# VGA.net
KiCad netlist of a schematic drawn in Altium Designer
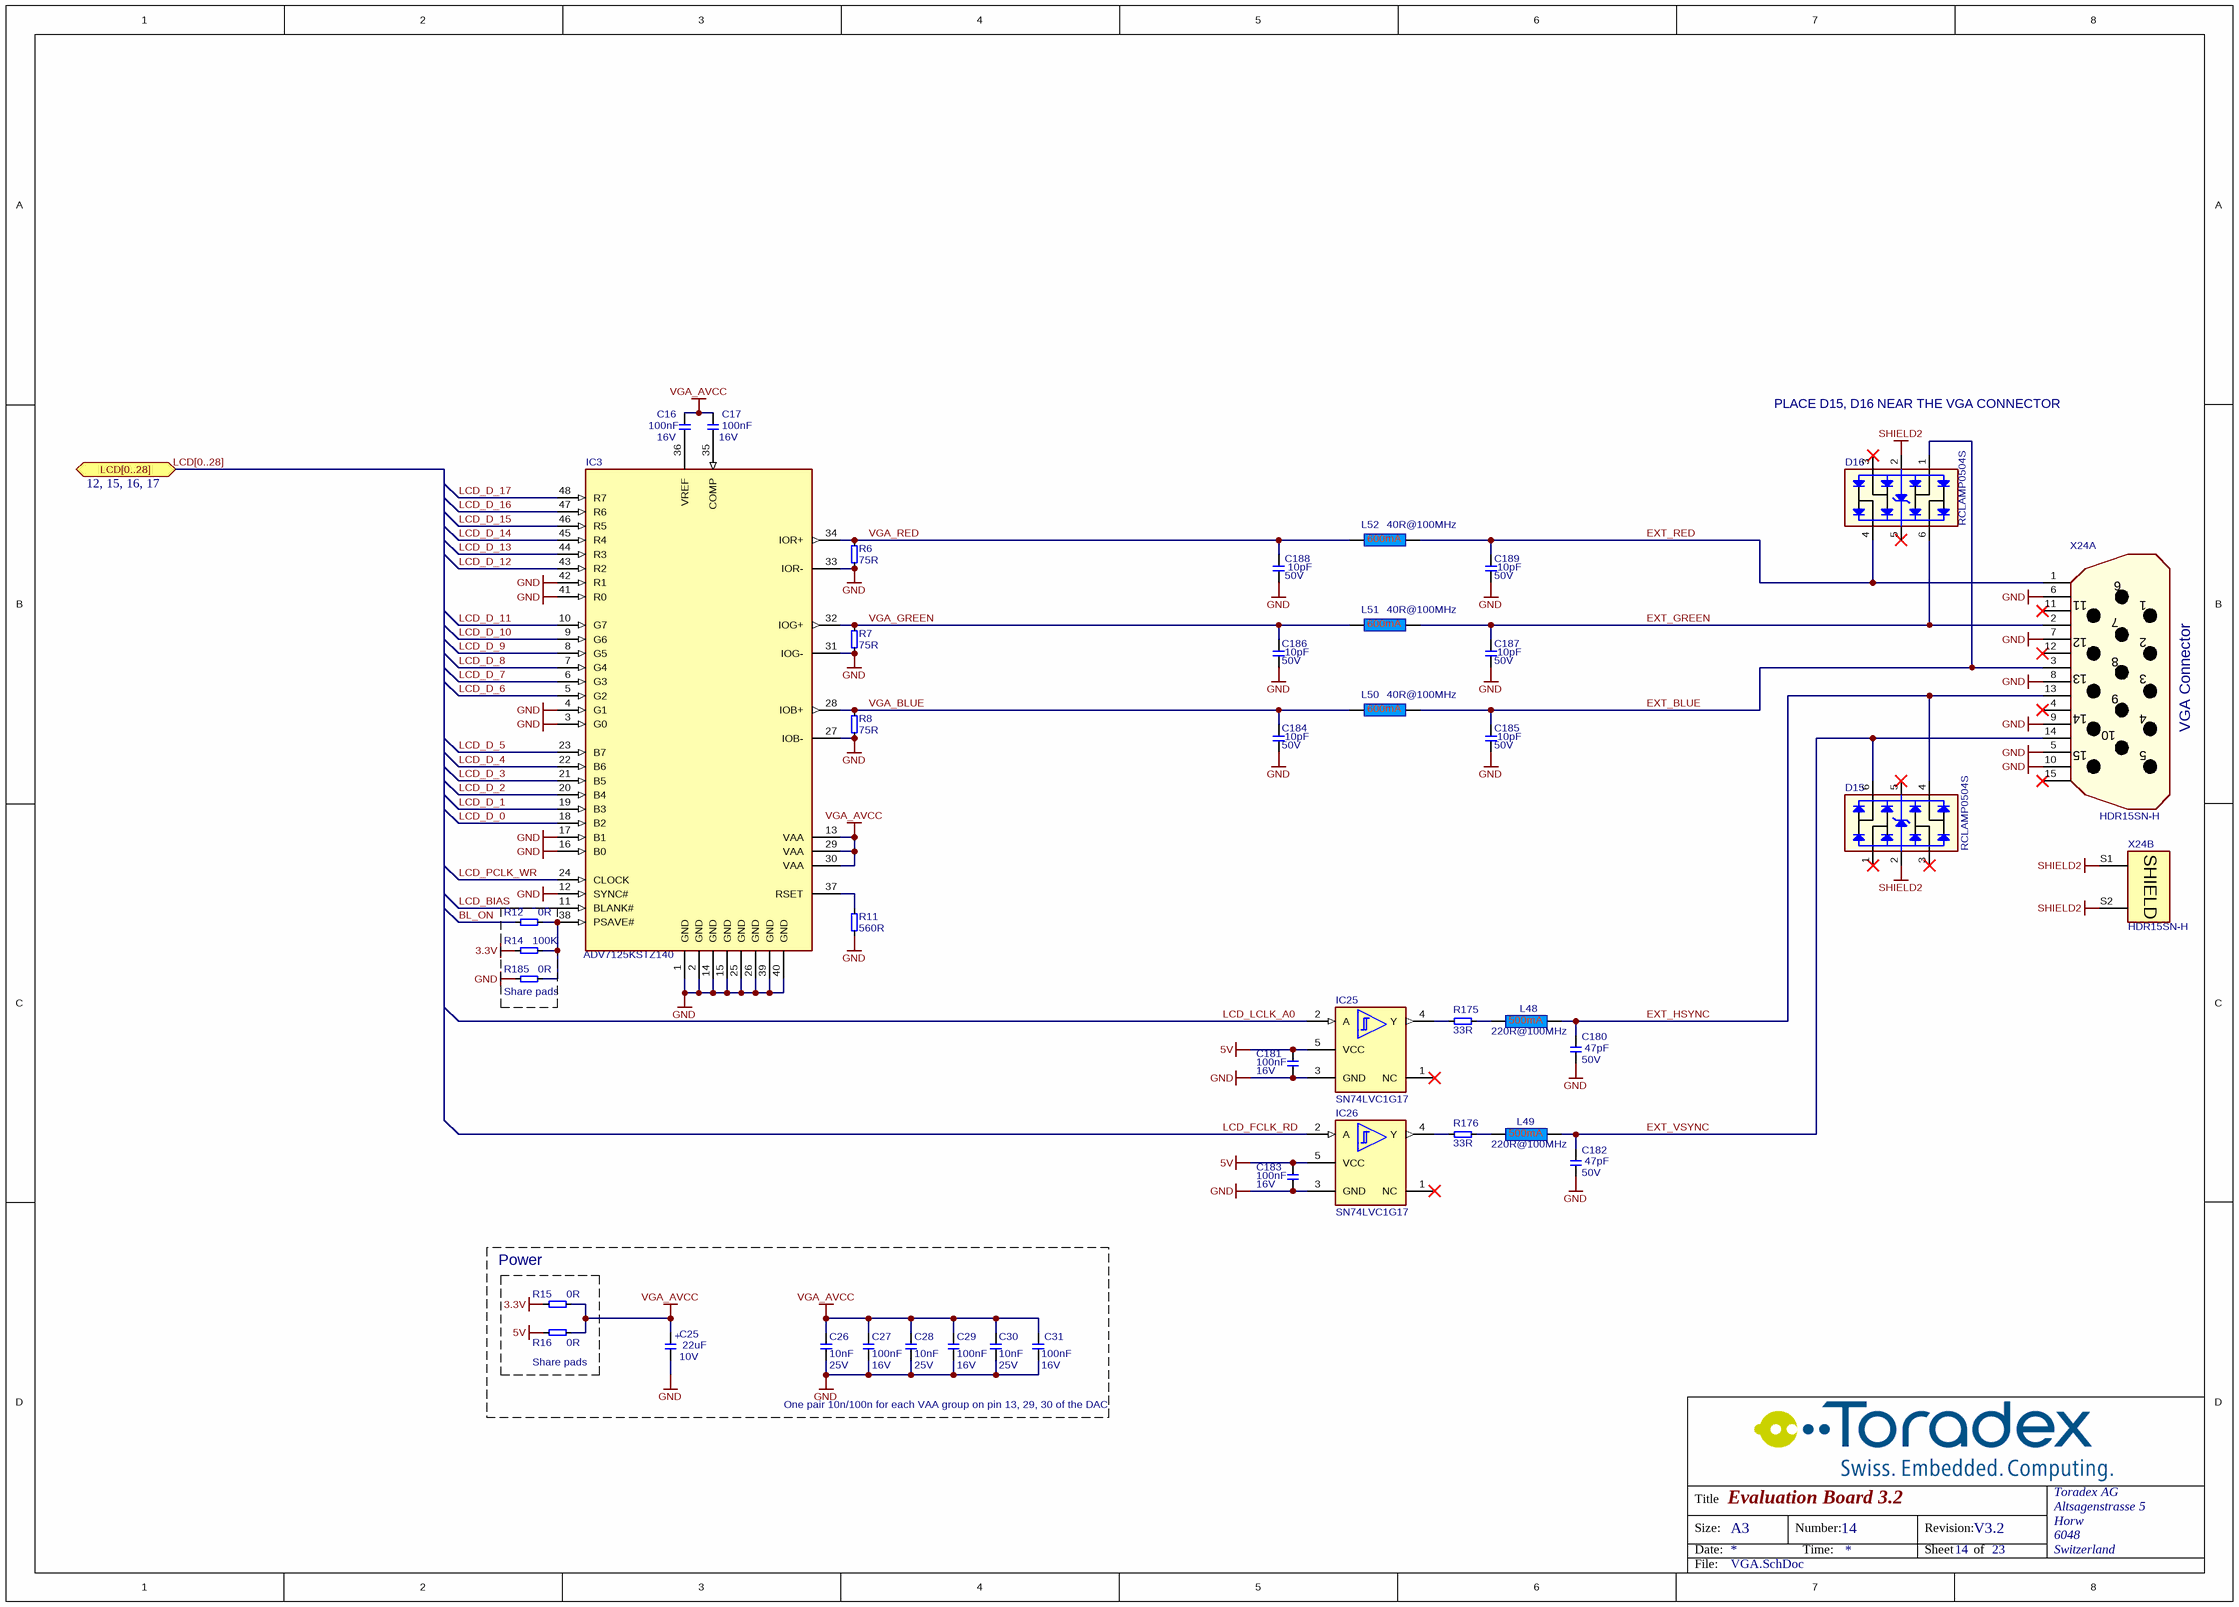
[diagram p0: VGA.SchDoc]

(export (version "E")
  (design (tool "Eeschema 10.0.6"))
  (components
    (comp (ref "C16")
      (value "100nF")
      (footprint "T_CAPC0603X33N")
      (description "Capacitor Ceramic X7R 100nF 16V 10% 0603")
      (fields (field (name "TOLERANCE") "10%") (field (name "RATING") "16V"))
      (libsource (lib "Evaluation Board") (part "C-X7R-100nF-16V-10%-0603"))
    )
    (comp (ref "C17")
      (value "100nF")
      (footprint "T_CAPC0603X33N")
      (description "Capacitor Ceramic X7R 100nF 16V 10% 0603")
      (fields (field (name "TOLERANCE") "10%") (field (name "RATING") "16V"))
      (libsource (lib "Evaluation Board") (part "C-X7R-100nF-16V-10%-0603"))
    )
    (comp (ref "C25")
      (value "22uF")
      (footprint "CAPMP3528X210N")
      (description "Capacitor TA 22uF 10V 20% 3528")
      (fields (field (name "TOLERANCE") "20%") (field (name "RATING") "10V"))
      (libsource (lib "Evaluation Board") (part "C-TA-22uF-10V-20%-3528"))
    )
    (comp (ref "C26")
      (value "10nF")
      (footprint "T_CAPC0603X33N")
      (description "Capacitor Ceramic X7R 10nF 25V 10% 0603")
      (fields (field (name "TOLERANCE") "10%") (field (name "RATING") "25V"))
      (libsource (lib "Evaluation Board") (part "C-X7R-10nF-25V-10%-0603"))
    )
    (comp (ref "C27")
      (value "100nF")
      (footprint "T_CAPC0603X33N")
      (description "Capacitor Ceramic X7R 100nF 16V 10% 0603")
      (fields (field (name "TOLERANCE") "10%") (field (name "RATING") "16V"))
      (libsource (lib "Evaluation Board") (part "C-X7R-100nF-16V-10%-0603"))
    )
    (comp (ref "C28")
      (value "10nF")
      (footprint "T_CAPC0603X33N")
      (description "Capacitor Ceramic X7R 10nF 25V 10% 0603")
      (fields (field (name "TOLERANCE") "10%") (field (name "RATING") "25V"))
      (libsource (lib "Evaluation Board") (part "C-X7R-10nF-25V-10%-0603"))
    )
    (comp (ref "C29")
      (value "100nF")
      (footprint "T_CAPC0603X33N")
      (description "Capacitor Ceramic X7R 100nF 16V 10% 0603")
      (fields (field (name "TOLERANCE") "10%") (field (name "RATING") "16V"))
      (libsource (lib "Evaluation Board") (part "C-X7R-100nF-16V-10%-0603"))
    )
    (comp (ref "C30")
      (value "10nF")
      (footprint "T_CAPC0603X33N")
      (description "Capacitor Ceramic X7R 10nF 25V 10% 0603")
      (fields (field (name "TOLERANCE") "10%") (field (name "RATING") "25V"))
      (libsource (lib "Evaluation Board") (part "C-X7R-10nF-25V-10%-0603"))
    )
    (comp (ref "C31")
      (value "100nF")
      (footprint "T_CAPC0603X33N")
      (description "Capacitor Ceramic X7R 100nF 16V 10% 0603")
      (fields (field (name "TOLERANCE") "10%") (field (name "RATING") "16V"))
      (libsource (lib "Evaluation Board") (part "C-X7R-100nF-16V-10%-0603"))
    )
    (comp (ref "C180")
      (value "47pF")
      (footprint "T_CAPC0603X33N")
      (description "Capacitor Ceramic NP0 47pF 50V 10% 0603")
      (fields (field (name "TOLERANCE") "10%") (field (name "RATING") "50V"))
      (libsource (lib "Evaluation Board") (part "C-NP0-47pF-50V-10%-0603"))
    )
    (comp (ref "C181")
      (value "100nF")
      (footprint "T_CAPC0603X33N")
      (description "Capacitor Ceramic X7R 100nF 16V 10% 0603")
      (fields (field (name "TOLERANCE") "10%") (field (name "RATING") "16V"))
      (libsource (lib "Evaluation Board") (part "C-X7R-100nF-16V-10%-0603"))
    )
    (comp (ref "C182")
      (value "47pF")
      (footprint "T_CAPC0603X33N")
      (description "Capacitor Ceramic NP0 47pF 50V 10% 0603")
      (fields (field (name "TOLERANCE") "10%") (field (name "RATING") "50V"))
      (libsource (lib "Evaluation Board") (part "C-NP0-47pF-50V-10%-0603"))
    )
    (comp (ref "C183")
      (value "100nF")
      (footprint "T_CAPC0603X33N")
      (description "Capacitor Ceramic X7R 100nF 16V 10% 0603")
      (fields (field (name "TOLERANCE") "10%") (field (name "RATING") "16V"))
      (libsource (lib "Evaluation Board") (part "C-X7R-100nF-16V-10%-0603"))
    )
    (comp (ref "C184")
      (value "10pF")
      (footprint "T_CAPC0603X33N")
      (description "Capacitor Ceramic NP0 10pF 50V 10% 0603")
      (fields (field (name "TOLERANCE") "10%") (field (name "RATING") "50V"))
      (libsource (lib "Evaluation Board") (part "C-NP0-10pF-50V-10%-0603"))
    )
    (comp (ref "C185")
      (value "10pF")
      (footprint "T_CAPC0603X33N")
      (description "Capacitor Ceramic NP0 10pF 50V 10% 0603")
      (fields (field (name "TOLERANCE") "10%") (field (name "RATING") "50V"))
      (libsource (lib "Evaluation Board") (part "C-NP0-10pF-50V-10%-0603"))
    )
    (comp (ref "C186")
      (value "10pF")
      (footprint "T_CAPC0603X33N")
      (description "Capacitor Ceramic NP0 10pF 50V 10% 0603")
      (fields (field (name "TOLERANCE") "10%") (field (name "RATING") "50V"))
      (libsource (lib "Evaluation Board") (part "C-NP0-10pF-50V-10%-0603"))
    )
    (comp (ref "C187")
      (value "10pF")
      (footprint "T_CAPC0603X33N")
      (description "Capacitor Ceramic NP0 10pF 50V 10% 0603")
      (fields (field (name "TOLERANCE") "10%") (field (name "RATING") "50V"))
      (libsource (lib "Evaluation Board") (part "C-NP0-10pF-50V-10%-0603"))
    )
    (comp (ref "C188")
      (value "10pF")
      (footprint "T_CAPC0603X33N")
      (description "Capacitor Ceramic NP0 10pF 50V 10% 0603")
      (fields (field (name "TOLERANCE") "10%") (field (name "RATING") "50V"))
      (libsource (lib "Evaluation Board") (part "C-NP0-10pF-50V-10%-0603"))
    )
    (comp (ref "C189")
      (value "10pF")
      (footprint "T_CAPC0603X33N")
      (description "Capacitor Ceramic NP0 10pF 50V 10% 0603")
      (fields (field (name "TOLERANCE") "10%") (field (name "RATING") "50V"))
      (libsource (lib "Evaluation Board") (part "C-NP0-10pF-50V-10%-0603"))
    )
    (comp (ref "D15")
      (value "RCLAMP0504S")
      (footprint "T_SOT95P285X90-6N")
      (description "TVS Array low cap")
      (fields (field (name "MANUFACTURER PART NO.") "RCLAMP0504S"))
      (libsource (lib "") (part "D-Semtech-RClamp0504S_1"))
    )
    (comp (ref "D16")
      (value "RCLAMP0504S")
      (footprint "T_SOT95P285X90-6N")
      (description "TVS Array low cap")
      (fields (field (name "MANUFACTURER PART NO.") "RCLAMP0504S"))
      (libsource (lib "Evaluation Board") (part "D-Semtech-RClamp0504S"))
    )
    (comp (ref "IC3")
      (value "ADV7125KSTZ140")
      (footprint "QFP50P900X900X120-48N")
      (description "Video DAC 8bit 140MHz")
      (fields (field (name "MANUFACTURER PART NO.") "ADV7125KSTZ140"))
      (libsource (lib "Evaluation Board") (part "IC-AD-ADV7125KSTZ140"))
    )
    (comp (ref "IC25")
      (value "SN74LVC1G17")
      (footprint "SOT65P210X110-5N")
      (description "Single Schmitt-Trigger Buffer")
      (fields (field (name "MANUFACTURER PART NO.") "SN74LVC1G17"))
      (libsource (lib "Evaluation Board") (part "IC-TI-SN74LVC1G17"))
    )
    (comp (ref "IC26")
      (value "SN74LVC1G17")
      (footprint "SOT65P210X110-5N")
      (description "Single Schmitt-Trigger Buffer")
      (fields (field (name "MANUFACTURER PART NO.") "SN74LVC1G17"))
      (libsource (lib "Evaluation Board") (part "IC-TI-SN74LVC1G17"))
    )
    (comp (ref "L48")
      (value "220R@100MHz")
      (footprint "INDC1608X95N")
      (description "220R@100MHz 500mA EMI FILTER")
      (fields (field (name "TOLERANCE") "25%"))
      (libsource (lib "Evaluation Board") (part "L-220R@100MHz-500mA-25%-0603"))
    )
    (comp (ref "L49")
      (value "220R@100MHz")
      (footprint "INDC1608X95N")
      (description "220R@100MHz 500mA EMI FILTER")
      (fields (field (name "TOLERANCE") "25%"))
      (libsource (lib "Evaluation Board") (part "L-220R@100MHz-500mA-25%-0603"))
    )
    (comp (ref "L50")
      (value "40R@100MHz")
      (footprint "INDC1608X95N")
      (description "40R@100MHz 600mA EMI FILTER")
      (fields (field (name "TOLERANCE") "25%") (field (name "MANUFACTURER PART NO.") "MMZ1608S400A"))
      (libsource (lib "Evaluation Board") (part "L-TDK-MMZ1608S400A-40R@100MHz-600mA-25%-0603"))
    )
    (comp (ref "L51")
      (value "40R@100MHz")
      (footprint "INDC1608X95N")
      (description "40R@100MHz 600mA EMI FILTER")
      (fields (field (name "TOLERANCE") "25%") (field (name "MANUFACTURER PART NO.") "MMZ1608S400A"))
      (libsource (lib "Evaluation Board") (part "L-TDK-MMZ1608S400A-40R@100MHz-600mA-25%-0603"))
    )
    (comp (ref "L52")
      (value "40R@100MHz")
      (footprint "INDC1608X95N")
      (description "40R@100MHz 600mA EMI FILTER")
      (fields (field (name "TOLERANCE") "25%") (field (name "MANUFACTURER PART NO.") "MMZ1608S400A"))
      (libsource (lib "Evaluation Board") (part "L-TDK-MMZ1608S400A-40R@100MHz-600mA-25%-0603"))
    )
    (comp (ref "R6")
      (value "75R")
      (footprint "T_RESC0603X30N")
      (description "Resistor 75 ohm 63mW 1% 0603")
      (fields (field (name "TOLERANCE") "1%"))
      (libsource (lib "Evaluation Board") (part "R-75R-63mW-1%-0603"))
    )
    (comp (ref "R7")
      (value "75R")
      (footprint "T_RESC0603X30N")
      (description "Resistor 75 ohm 63mW 1% 0603")
      (fields (field (name "TOLERANCE") "1%"))
      (libsource (lib "Evaluation Board") (part "R-75R-63mW-1%-0603"))
    )
    (comp (ref "R8")
      (value "75R")
      (footprint "T_RESC0603X30N")
      (description "Resistor 75 ohm 63mW 1% 0603")
      (fields (field (name "TOLERANCE") "1%"))
      (libsource (lib "Evaluation Board") (part "R-75R-63mW-1%-0603"))
    )
    (comp (ref "R11")
      (value "560R")
      (footprint "t_RESC0603X30N")
      (description "Resistor 560 ohm 63mW 5% 0603")
      (fields (field (name "TOLERANCE") "5%"))
      (libsource (lib "Evaluation Board") (part "R-560R-63mW-5%-0603"))
    )
    (comp (ref "R12")
      (value "0R")
      (footprint "T_RESC0603X30N")
      (description "Resistor 0 ohm 63mW 1% 0603")
      (fields (field (name "TOLERANCE") "1%"))
      (libsource (lib "Evaluation Board") (part "R-0R-63mW-1%-0603"))
    )
    (comp (ref "R14")
      (value "100K")
      (footprint "T_RESC0603X30N")
      (description "Resistor 100 Kohm 63mW 5% 0603")
      (fields (field (name "TOLERANCE") "5%"))
      (libsource (lib "Evaluation Board") (part "R-100KR-63mW-5%-0603"))
    )
    (comp (ref "R15")
      (value "0R")
      (footprint "T_RESC0603X30N")
      (description "Resistor 0 ohm 63mW 1% 0603")
      (fields (field (name "TOLERANCE") "1%"))
      (libsource (lib "Evaluation Board") (part "R-0R-63mW-1%-0603"))
    )
    (comp (ref "R16")
      (value "0R")
      (footprint "T_RESC0603X30N")
      (description "Resistor 0 ohm 63mW 1% 0603")
      (fields (field (name "TOLERANCE") "1%"))
      (libsource (lib "Evaluation Board") (part "R-0R-63mW-1%-0603"))
    )
    (comp (ref "R175")
      (value "33R")
      (footprint "t_RESC0603X30N")
      (description "Resistor 33 ohm 63mW 5% 0603")
      (fields (field (name "TOLERANCE") "5%"))
      (libsource (lib "Evaluation Board") (part "R-33R-63mW-5%-0603"))
    )
    (comp (ref "R176")
      (value "33R")
      (footprint "t_RESC0603X30N")
      (description "Resistor 33 ohm 63mW 5% 0603")
      (fields (field (name "TOLERANCE") "5%"))
      (libsource (lib "Evaluation Board") (part "R-33R-63mW-5%-0603"))
    )
    (comp (ref "R185")
      (value "0R")
      (footprint "t_RESC0603X30N")
      (description "Resistor 0 ohm 63mW 1% 0603")
      (fields (field (name "TOLERANCE") "1%"))
      (libsource (lib "Evaluation Board") (part "R-0R-63mW-1%-0603"))
    )
    (comp (ref "X24")
      (value "HDR15SN-H")
      (footprint "T_AUK_HDR15SN-H")
      (description "15 pin male D-SUB connector")
      (fields (field (name "MANUFACTURER PART NO.") "HDR15SN-H"))
      (libsource (lib "") (part "CON-AUK-HDR15SN-H_1"))
    )
  )
  (nets
    (net (code "30") (name "/BL_ON") (class "Default")
      (node (ref "R12") (pin "1") (pinfunction "1_1") (pintype "passive"))
    )
    (net (code "31") (name "/EXT_BLUE") (class "Default")
      (node (ref "C185") (pin "1") (pinfunction "1_1") (pintype "passive"))
      (node (ref "D16") (pin "1") (pinfunction "1_1") (pintype "power_in"))
      (node (ref "L50") (pin "2") (pinfunction "2_2") (pintype "passive"))
      (node (ref "X24") (pin "3") (pinfunction "TXD_3") (pintype "passive"))
    )
    (net (code "32") (name "/EXT_GREEN") (class "Default")
      (node (ref "C187") (pin "1") (pinfunction "1_1") (pintype "passive"))
      (node (ref "D16") (pin "6") (pinfunction "6_6") (pintype "power_in"))
      (node (ref "L51") (pin "2") (pinfunction "2_2") (pintype "passive"))
      (node (ref "X24") (pin "2") (pinfunction "RXD_2") (pintype "passive"))
    )
    (net (code "33") (name "/EXT_HSYNC") (class "Default")
      (node (ref "C180") (pin "1") (pinfunction "1_1") (pintype "passive"))
      (node (ref "D15") (pin "4") (pinfunction "4_4") (pintype "power_in"))
      (node (ref "L48") (pin "2") (pinfunction "2_2") (pintype "passive"))
      (node (ref "X24") (pin "13") (pinfunction "RI_13") (pintype "passive"))
    )
    (net (code "34") (name "/EXT_RED") (class "Default")
      (node (ref "C189") (pin "1") (pinfunction "1_1") (pintype "passive"))
      (node (ref "D16") (pin "4") (pinfunction "4_4") (pintype "power_in"))
      (node (ref "L52") (pin "2") (pinfunction "2_2") (pintype "passive"))
      (node (ref "X24") (pin "1") (pinfunction "DCD_1") (pintype "passive"))
    )
    (net (code "35") (name "/EXT_VSYNC") (class "Default")
      (node (ref "C182") (pin "1") (pinfunction "1_1") (pintype "passive"))
      (node (ref "D15") (pin "6") (pinfunction "6_6") (pintype "power_in"))
      (node (ref "L49") (pin "2") (pinfunction "2_2") (pintype "passive"))
      (node (ref "X24") (pin "14") (pinfunction "RI_14") (pintype "passive"))
    )
    (net (code "37") (name "/LCD_BIAS") (class "Default")
      (node (ref "IC3") (pin "11") (pinfunction "BLANK#_11") (pintype "input"))
    )
    (net (code "38") (name "/LCD_D_0") (class "Default")
      (node (ref "IC3") (pin "18") (pinfunction "B2_18") (pintype "input"))
    )
    (net (code "39") (name "/LCD_D_1") (class "Default")
      (node (ref "IC3") (pin "19") (pinfunction "B3_19") (pintype "input"))
    )
    (net (code "40") (name "/LCD_D_2") (class "Default")
      (node (ref "IC3") (pin "20") (pinfunction "B4_20") (pintype "input"))
    )
    (net (code "41") (name "/LCD_D_3") (class "Default")
      (node (ref "IC3") (pin "21") (pinfunction "B5_21") (pintype "input"))
    )
    (net (code "42") (name "/LCD_D_4") (class "Default")
      (node (ref "IC3") (pin "22") (pinfunction "B6_22") (pintype "input"))
    )
    (net (code "43") (name "/LCD_D_5") (class "Default")
      (node (ref "IC3") (pin "23") (pinfunction "B7_23") (pintype "input"))
    )
    (net (code "44") (name "/LCD_D_6") (class "Default")
      (node (ref "IC3") (pin "5") (pinfunction "G2_5") (pintype "input"))
    )
    (net (code "45") (name "/LCD_D_7") (class "Default")
      (node (ref "IC3") (pin "6") (pinfunction "G3_6") (pintype "input"))
    )
    (net (code "46") (name "/LCD_D_8") (class "Default")
      (node (ref "IC3") (pin "7") (pinfunction "G4_7") (pintype "input"))
    )
    (net (code "47") (name "/LCD_D_9") (class "Default")
      (node (ref "IC3") (pin "8") (pinfunction "G5_8") (pintype "input"))
    )
    (net (code "48") (name "/LCD_D_10") (class "Default")
      (node (ref "IC3") (pin "9") (pinfunction "G6_9") (pintype "input"))
    )
    (net (code "49") (name "/LCD_D_11") (class "Default")
      (node (ref "IC3") (pin "10") (pinfunction "G7_10") (pintype "input"))
    )
    (net (code "50") (name "/LCD_D_12") (class "Default")
      (node (ref "IC3") (pin "43") (pinfunction "R2_43") (pintype "input"))
    )
    (net (code "51") (name "/LCD_D_13") (class "Default")
      (node (ref "IC3") (pin "44") (pinfunction "R3_44") (pintype "input"))
    )
    (net (code "52") (name "/LCD_D_14") (class "Default")
      (node (ref "IC3") (pin "45") (pinfunction "R4_45") (pintype "input"))
    )
    (net (code "53") (name "/LCD_D_15") (class "Default")
      (node (ref "IC3") (pin "46") (pinfunction "R5_46") (pintype "input"))
    )
    (net (code "54") (name "/LCD_D_16") (class "Default")
      (node (ref "IC3") (pin "47") (pinfunction "R6_47") (pintype "input"))
    )
    (net (code "55") (name "/LCD_D_17") (class "Default")
      (node (ref "IC3") (pin "48") (pinfunction "R7_48") (pintype "input"))
    )
    (net (code "56") (name "/LCD_FCLK_RD") (class "Default")
      (node (ref "IC26") (pin "2") (pinfunction "A_2") (pintype "input"))
    )
    (net (code "57") (name "/LCD_LCLK_A0") (class "Default")
      (node (ref "IC25") (pin "2") (pinfunction "A_2") (pintype "input"))
    )
    (net (code "58") (name "/LCD_PCLK_WR") (class "Default")
      (node (ref "IC3") (pin "24") (pinfunction "CLOCK_24") (pintype "input"))
    )
    (net (code "59") (name "/VGA_BLUE") (class "Default")
      (node (ref "C184") (pin "1") (pinfunction "1_1") (pintype "passive"))
      (node (ref "IC3") (pin "28") (pinfunction "IOB+_28") (pintype "output"))
      (node (ref "L50") (pin "1") (pinfunction "1_1") (pintype "passive"))
      (node (ref "R8") (pin "2") (pinfunction "2_2") (pintype "passive"))
    )
    (net (code "60") (name "/VGA_GREEN") (class "Default")
      (node (ref "C186") (pin "1") (pinfunction "1_1") (pintype "passive"))
      (node (ref "IC3") (pin "32") (pinfunction "IOG+_32") (pintype "output"))
      (node (ref "L51") (pin "1") (pinfunction "1_1") (pintype "passive"))
      (node (ref "R7") (pin "2") (pinfunction "2_2") (pintype "passive"))
    )
    (net (code "61") (name "/VGA_RED") (class "Default")
      (node (ref "C188") (pin "1") (pinfunction "1_1") (pintype "passive"))
      (node (ref "IC3") (pin "34") (pinfunction "IOR+_34") (pintype "output"))
      (node (ref "L52") (pin "1") (pinfunction "1_1") (pintype "passive"))
      (node (ref "R6") (pin "2") (pinfunction "2_2") (pintype "passive"))
    )
    (net (code "62") (name "3.3V") (class "Default")
      (node (ref "R14") (pin "1") (pinfunction "1_1") (pintype "passive"))
      (node (ref "R15") (pin "1") (pinfunction "1_1") (pintype "passive"))
    )
    (net (code "63") (name "5V") (class "Default")
      (node (ref "C181") (pin "2") (pinfunction "2_2") (pintype "passive"))
      (node (ref "C183") (pin "2") (pinfunction "2_2") (pintype "passive"))
      (node (ref "IC25") (pin "5") (pinfunction "VCC_5") (pintype "power_in"))
      (node (ref "IC26") (pin "5") (pinfunction "VCC_5") (pintype "power_in"))
      (node (ref "R16") (pin "1") (pinfunction "1_1") (pintype "passive"))
    )
    (net (code "64") (name "GND") (class "Default")
      (node (ref "C180") (pin "2") (pinfunction "2_2") (pintype "passive"))
      (node (ref "C181") (pin "1") (pinfunction "1_1") (pintype "passive"))
      (node (ref "C182") (pin "2") (pinfunction "2_2") (pintype "passive"))
      (node (ref "C183") (pin "1") (pinfunction "1_1") (pintype "passive"))
      (node (ref "C184") (pin "2") (pinfunction "2_2") (pintype "passive"))
      (node (ref "C185") (pin "2") (pinfunction "2_2") (pintype "passive"))
      (node (ref "C186") (pin "2") (pinfunction "2_2") (pintype "passive"))
      (node (ref "C187") (pin "2") (pinfunction "2_2") (pintype "passive"))
      (node (ref "C188") (pin "2") (pinfunction "2_2") (pintype "passive"))
      (node (ref "C189") (pin "2") (pinfunction "2_2") (pintype "passive"))
      (node (ref "C25") (pin "2") (pinfunction "2_2") (pintype "passive"))
      (node (ref "C26") (pin "1") (pinfunction "1_1") (pintype "passive"))
      (node (ref "C27") (pin "1") (pinfunction "1_1") (pintype "passive"))
      (node (ref "C28") (pin "1") (pinfunction "1_1") (pintype "passive"))
      (node (ref "C29") (pin "1") (pinfunction "1_1") (pintype "passive"))
      (node (ref "C30") (pin "1") (pinfunction "1_1") (pintype "passive"))
      (node (ref "C31") (pin "1") (pinfunction "1_1") (pintype "passive"))
      (node (ref "IC25") (pin "3") (pinfunction "GND_3") (pintype "power_in"))
      (node (ref "IC26") (pin "3") (pinfunction "GND_3") (pintype "power_in"))
      (node (ref "IC3") (pin "1") (pinfunction "GND_1") (pintype "power_in"))
      (node (ref "IC3") (pin "12") (pinfunction "SYNC#_12") (pintype "input"))
      (node (ref "IC3") (pin "14") (pinfunction "GND_14") (pintype "power_in"))
      (node (ref "IC3") (pin "15") (pinfunction "GND_15") (pintype "power_in"))
      (node (ref "IC3") (pin "16") (pinfunction "B0_16") (pintype "input"))
      (node (ref "IC3") (pin "17") (pinfunction "B1_17") (pintype "input"))
      (node (ref "IC3") (pin "2") (pinfunction "GND_2") (pintype "power_in"))
      (node (ref "IC3") (pin "25") (pinfunction "GND_25") (pintype "power_in"))
      (node (ref "IC3") (pin "26") (pinfunction "GND_26") (pintype "power_in"))
      (node (ref "IC3") (pin "27") (pinfunction "IOB-_27") (pintype "power_in"))
      (node (ref "IC3") (pin "3") (pinfunction "G0_3") (pintype "input"))
      (node (ref "IC3") (pin "31") (pinfunction "IOG-_31") (pintype "power_in"))
      (node (ref "IC3") (pin "33") (pinfunction "IOR-_33") (pintype "power_in"))
      (node (ref "IC3") (pin "39") (pinfunction "GND_39") (pintype "power_in"))
      (node (ref "IC3") (pin "4") (pinfunction "G1_4") (pintype "input"))
      (node (ref "IC3") (pin "40") (pinfunction "GND_40") (pintype "power_in"))
      (node (ref "IC3") (pin "41") (pinfunction "R0_41") (pintype "input"))
      (node (ref "IC3") (pin "42") (pinfunction "R1_42") (pintype "input"))
      (node (ref "R11") (pin "1") (pinfunction "1_1") (pintype "passive"))
      (node (ref "R185") (pin "1") (pinfunction "1_1") (pintype "passive"))
      (node (ref "R6") (pin "1") (pinfunction "1_1") (pintype "passive"))
      (node (ref "R7") (pin "1") (pinfunction "1_1") (pintype "passive"))
      (node (ref "R8") (pin "1") (pinfunction "1_1") (pintype "passive"))
      (node (ref "X24") (pin "10") (pinfunction "RI_10") (pintype "passive"))
      (node (ref "X24") (pin "5") (pinfunction "GND_5") (pintype "passive"))
      (node (ref "X24") (pin "6") (pinfunction "DSR_6") (pintype "passive"))
      (node (ref "X24") (pin "7") (pinfunction "RTS_7") (pintype "passive"))
      (node (ref "X24") (pin "8") (pinfunction "CTS_8") (pintype "passive"))
      (node (ref "X24") (pin "9") (pinfunction "RI_9") (pintype "passive"))
    )
    (net (code "65") (name "Net-(IC3-COMP)") (class "Default")
      (node (ref "C17") (pin "2") (pinfunction "2_2") (pintype "passive"))
      (node (ref "IC3") (pin "35") (pinfunction "COMP_35") (pintype "input"))
    )
    (net (code "66") (name "Net-(IC3-PSAVE#)") (class "Default")
      (node (ref "IC3") (pin "38") (pinfunction "PSAVE#_38") (pintype "input"))
      (node (ref "R12") (pin "2") (pinfunction "2_2") (pintype "passive"))
      (node (ref "R14") (pin "2") (pinfunction "2_2") (pintype "passive"))
      (node (ref "R185") (pin "2") (pinfunction "2_2") (pintype "passive"))
    )
    (net (code "67") (name "Net-(IC3-RSET)") (class "Default")
      (node (ref "IC3") (pin "37") (pinfunction "RSET_37") (pintype "passive"))
      (node (ref "R11") (pin "2") (pinfunction "2_2") (pintype "passive"))
    )
    (net (code "68") (name "Net-(IC3-VREF)") (class "Default")
      (node (ref "C16") (pin "2") (pinfunction "2_2") (pintype "passive"))
      (node (ref "IC3") (pin "36") (pinfunction "VREF_36") (pintype "power_in"))
    )
    (net (code "69") (name "Net-(IC25-Y)") (class "Default")
      (node (ref "IC25") (pin "4") (pinfunction "Y_4") (pintype "output"))
      (node (ref "R175") (pin "1") (pinfunction "1_1") (pintype "passive"))
    )
    (net (code "70") (name "Net-(IC26-Y)") (class "Default")
      (node (ref "IC26") (pin "4") (pinfunction "Y_4") (pintype "output"))
      (node (ref "R176") (pin "1") (pinfunction "1_1") (pintype "passive"))
    )
    (net (code "71") (name "Net-(L48-Pad1)") (class "Default")
      (node (ref "L48") (pin "1") (pinfunction "1_1") (pintype "passive"))
      (node (ref "R175") (pin "2") (pinfunction "2_2") (pintype "passive"))
    )
    (net (code "72") (name "Net-(L49-Pad1)") (class "Default")
      (node (ref "L49") (pin "1") (pinfunction "1_1") (pintype "passive"))
      (node (ref "R176") (pin "2") (pinfunction "2_2") (pintype "passive"))
    )
    (net (code "73") (name "SHIELD2") (class "Default")
      (node (ref "D15") (pin "2") (pinfunction "2_2") (pintype "power_in"))
      (node (ref "D16") (pin "2") (pinfunction "2_2") (pintype "power_in"))
      (node (ref "X24") (pin "S1") (pinfunction "SHIELD_S1") (pintype "passive"))
      (node (ref "X24") (pin "S2") (pinfunction "SHIELD_S2") (pintype "passive"))
    )
    (net (code "74") (name "VGA_AVCC") (class "Default")
      (node (ref "C16") (pin "1") (pinfunction "1_1") (pintype "passive"))
      (node (ref "C17") (pin "1") (pinfunction "1_1") (pintype "passive"))
      (node (ref "C25") (pin "1") (pinfunction "1_1") (pintype "passive"))
      (node (ref "C26") (pin "2") (pinfunction "2_2") (pintype "passive"))
      (node (ref "C27") (pin "2") (pinfunction "2_2") (pintype "passive"))
      (node (ref "C28") (pin "2") (pinfunction "2_2") (pintype "passive"))
      (node (ref "C29") (pin "2") (pinfunction "2_2") (pintype "passive"))
      (node (ref "C30") (pin "2") (pinfunction "2_2") (pintype "passive"))
      (node (ref "C31") (pin "2") (pinfunction "2_2") (pintype "passive"))
      (node (ref "IC3") (pin "13") (pinfunction "VAA_13") (pintype "power_in"))
      (node (ref "IC3") (pin "29") (pinfunction "VAA_29") (pintype "power_in"))
      (node (ref "IC3") (pin "30") (pinfunction "VAA_30") (pintype "power_in"))
      (node (ref "R15") (pin "2") (pinfunction "2_2") (pintype "passive"))
      (node (ref "R16") (pin "2") (pinfunction "2_2") (pintype "passive"))
    )
    (net (code "75") (name "unconnected-(D15-Pad1)") (class "Default")
      (node (ref "D15") (pin "1") (pinfunction "1_1") (pintype "power_in+no_connect"))
    )
    (net (code "76") (name "unconnected-(D15-Pad3)") (class "Default")
      (node (ref "D15") (pin "3") (pinfunction "3_3") (pintype "power_in+no_connect"))
    )
    (net (code "77") (name "unconnected-(D15-Pad5)") (class "Default")
      (node (ref "D15") (pin "5") (pinfunction "5_5") (pintype "power_in+no_connect"))
    )
    (net (code "78") (name "unconnected-(D16-Pad3)") (class "Default")
      (node (ref "D16") (pin "3") (pinfunction "3_3") (pintype "power_in+no_connect"))
    )
    (net (code "79") (name "unconnected-(D16-Pad5)") (class "Default")
      (node (ref "D16") (pin "5") (pinfunction "5_5") (pintype "power_in+no_connect"))
    )
    (net (code "80") (name "unconnected-(IC25-NC-Pad1)") (class "Default")
      (node (ref "IC25") (pin "1") (pinfunction "NC_1") (pintype "passive+no_connect"))
    )
    (net (code "81") (name "unconnected-(IC26-NC-Pad1)") (class "Default")
      (node (ref "IC26") (pin "1") (pinfunction "NC_1") (pintype "passive+no_connect"))
    )
    (net (code "82") (name "unconnected-(X24A-DTR-Pad4)") (class "Default")
      (node (ref "X24") (pin "4") (pinfunction "DTR_4") (pintype "passive+no_connect"))
    )
    (net (code "83") (name "unconnected-(X24A-RI-Pad11)") (class "Default")
      (node (ref "X24") (pin "11") (pinfunction "RI_11") (pintype "passive+no_connect"))
    )
    (net (code "84") (name "unconnected-(X24A-RI-Pad12)") (class "Default")
      (node (ref "X24") (pin "12") (pinfunction "RI_12") (pintype "passive+no_connect"))
    )
    (net (code "85") (name "unconnected-(X24A-RI-Pad15)") (class "Default")
      (node (ref "X24") (pin "15") (pinfunction "RI_15") (pintype "passive+no_connect"))
    )
  )
)
